# plugV6.net
KiCad netlist of a schematic drawn in EAGLE
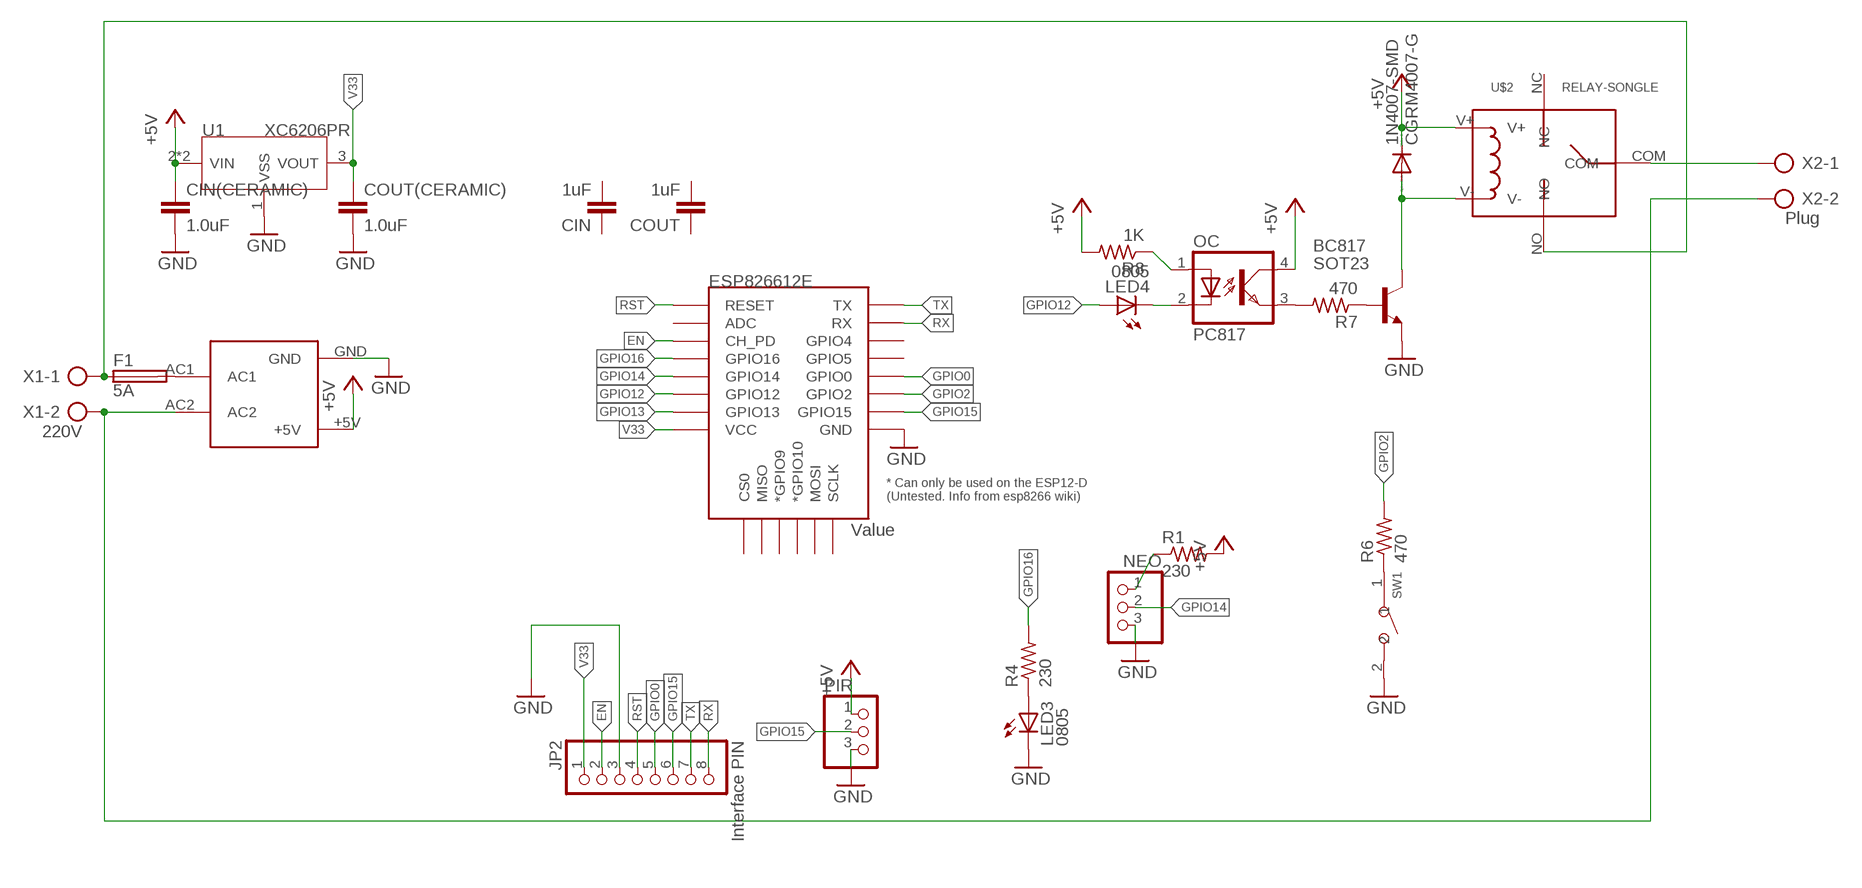
[diagram p0: schematic, sheet 1]

(export (version "E")
  (design (tool "Eeschema 10.0.6"))
  (components
    (comp (ref "1N4007-SMD")
      (value "CGRM4007-G")
      (footprint "eagle-import:SOD-123_MINI-SMA")
      (libsource (lib "eagle-import") (part "CGRM400-G7"))
    )
    (comp (ref "BC817")
      (value "SOT23")
      (footprint "eagle-import:SOT23-BEC")
      (libsource (lib "eagle-import") (part "-NPN-SOT23-BECBC817"))
    )
    (comp (ref "CIN")
      (value "1uF")
      (footprint "eagle-import:C0805")
      (libsource (lib "eagle-import") (part "C-EUC0805"))
    )
    (comp (ref "CIN(CERAMIC)")
      (value "1.0uF")
      (footprint "eagle-import:0402-CAP")
      (libsource (lib "eagle-import") (part "1.0UF-16V-10%(0402)"))
    )
    (comp (ref "COUT")
      (value "1uF")
      (footprint "eagle-import:C0805")
      (libsource (lib "eagle-import") (part "C-EUC0805"))
    )
    (comp (ref "COUT(CERAMIC)")
      (value "1.0uF")
      (footprint "eagle-import:0402-CAP")
      (libsource (lib "eagle-import") (part "1.0UF-16V-10%(0402)"))
    )
    (comp (ref "ESP826612E")
      (value "Value")
      (footprint "eagle-import:ESP12E-SMD")
      (libsource (lib "eagle-import") (part "ESP12ESMD"))
    )
    (comp (ref "F1")
      (value "5A")
      (footprint "eagle-import:SH22,5A")
      (fields (field (name "MPN") "0031.7701.11"))
      (libsource (lib "eagle-import") (part "SH22,5A"))
    )
    (comp (ref "JP2")
      (value "Interface PIN")
      (footprint "eagle-import:1X08")
      (libsource (lib "eagle-import") (part "PINHD-1X8"))
    )
    (comp (ref "LED3")
      (value "0805")
      (footprint "eagle-import:CHIP-LED0603")
      (libsource (lib "eagle-import") (part "LEDCHIP-LED0603"))
    )
    (comp (ref "LED4")
      (value "0805")
      (footprint "eagle-import:CHIP-LED0603")
      (libsource (lib "eagle-import") (part "LEDCHIP-LED0603"))
    )
    (comp (ref "NEO")
      (value "PINHD-1X3")
      (footprint "eagle-import:1X03")
      (libsource (lib "eagle-import") (part "PINHD-1X3"))
    )
    (comp (ref "OC")
      (value "PC817")
      (footprint "eagle-import:DIL04")
      (fields (field (name "MPN") "PC817X4J000F"))
      (libsource (lib "eagle-import") (part "PC817"))
    )
    (comp (ref "PIR")
      (value "PINHD-1X3")
      (footprint "eagle-import:1X03")
      (libsource (lib "eagle-import") (part "PINHD-1X3"))
    )
    (comp (ref "R1")
      (value "230")
      (footprint "eagle-import:R1206")
      (libsource (lib "eagle-import") (part "R-US_R1206"))
    )
    (comp (ref "R4")
      (value "230")
      (footprint "eagle-import:R1206")
      (libsource (lib "eagle-import") (part "R-US_R1206"))
    )
    (comp (ref "R6")
      (value "470")
      (footprint "eagle-import:R1206")
      (libsource (lib "eagle-import") (part "R-US_R1206"))
    )
    (comp (ref "R7")
      (value "470")
      (footprint "eagle-import:R1206")
      (libsource (lib "eagle-import") (part "R-US_R1206"))
    )
    (comp (ref "R8")
      (value "1K")
      (footprint "eagle-import:R1206")
      (libsource (lib "eagle-import") (part "R-US_R1206"))
    )
    (comp (ref "SW1")
      (value "DIP-BUTTON(2P-6.0X3.0X4.3MM)-TS-1101F")
      (footprint "eagle-import:SW2-5.0-6.0X3.0X4.3MM")
      (libsource (lib "eagle-import") (part "DIP-BUTTON(2P-6.0X3.0X4.3MM)-TS-1101F"))
    )
    (comp (ref "U$1")
      (value "HLK-PM01")
      (footprint "eagle-import:HLK-PM01")
      (libsource (lib "eagle-import") (part "HLK-PM01"))
    )
    (comp (ref "U$2")
      (value "RELAY-SONGLE")
      (footprint "eagle-import:RELAY-SONGLE")
      (libsource (lib "eagle-import") (part "RELAY-SONGLE"))
    )
    (comp (ref "U1")
      (value "XC6206PR")
      (footprint "eagle-import:SOT89")
      (libsource (lib "eagle-import") (part "XC6206PR"))
    )
    (comp (ref "X1")
      (value "220V")
      (footprint "eagle-import:AK300_2")
      (libsource (lib "eagle-import") (part "AK300/2"))
    )
    (comp (ref "X2")
      (value "Plug")
      (footprint "eagle-import:AK300_2")
      (libsource (lib "eagle-import") (part "AK300/2"))
    )
  )
  (nets
    (net (code "1") (name "+5V") (class "Default")
      (node (ref "1N4007-SMD") (pin "C") (pinfunction "C_C") (pintype "passive"))
      (node (ref "CIN(CERAMIC)") (pin "1") (pinfunction "1_1") (pintype "passive"))
      (node (ref "OC") (pin "4") (pinfunction "COL_4") (pintype "passive"))
      (node (ref "PIR") (pin "1") (pinfunction "1_1") (pintype "passive"))
      (node (ref "R1") (pin "2") (pinfunction "2_2") (pintype "passive"))
      (node (ref "R8") (pin "2") (pinfunction "2_2") (pintype "passive"))
      (node (ref "U$1") (pin "+5V") (pinfunction "+5V_+5V") (pintype "bidirectional"))
      (node (ref "U$2") (pin "V+") (pinfunction "V+_V+") (pintype "bidirectional"))
      (node (ref "U1") (pin "2") (pinfunction "VIN_2") (pintype "input"))
      (node (ref "U1") (pin "4") (pinfunction "VIN_4") (pintype "input"))
    )
    (net (code "2") (name "EN") (class "Default")
      (node (ref "ESP826612E") (pin "CH_PD") (pinfunction "CH_PD_CH_PD") (pintype "bidirectional"))
      (node (ref "JP2") (pin "2") (pinfunction "2_2") (pintype "passive"))
    )
    (net (code "3") (name "GND") (class "Default")
      (node (ref "BC817") (pin "E") (pinfunction "E_E") (pintype "passive"))
      (node (ref "CIN(CERAMIC)") (pin "2") (pinfunction "2_2") (pintype "passive"))
      (node (ref "COUT(CERAMIC)") (pin "2") (pinfunction "2_2") (pintype "passive"))
      (node (ref "ESP826612E") (pin "GND") (pinfunction "GND_GND") (pintype "bidirectional"))
      (node (ref "JP2") (pin "3") (pinfunction "3_3") (pintype "passive"))
      (node (ref "LED3") (pin "C") (pinfunction "C_C") (pintype "passive"))
      (node (ref "NEO") (pin "3") (pinfunction "3_3") (pintype "passive"))
      (node (ref "PIR") (pin "3") (pinfunction "3_3") (pintype "passive"))
      (node (ref "SW1") (pin "2") (pinfunction "2_2") (pintype "bidirectional"))
      (node (ref "U$1") (pin "GND") (pinfunction "GND_GND") (pintype "bidirectional"))
      (node (ref "U1") (pin "1") (pinfunction "VSS_1") (pintype "power_in"))
    )
    (net (code "4") (name "GPIO0") (class "Default")
      (node (ref "ESP826612E") (pin "GPIO0") (pinfunction "GPIO0_GPIO0") (pintype "bidirectional"))
      (node (ref "JP2") (pin "5") (pinfunction "5_5") (pintype "passive"))
    )
    (net (code "5") (name "GPIO2") (class "Default")
      (node (ref "ESP826612E") (pin "GPIO2") (pinfunction "GPIO2_GPIO2") (pintype "bidirectional"))
      (node (ref "R6") (pin "2") (pinfunction "2_2") (pintype "passive"))
    )
    (net (code "6") (name "GPIO12") (class "Default")
      (node (ref "ESP826612E") (pin "GPIO12") (pinfunction "GPIO12_GPIO12") (pintype "bidirectional"))
      (node (ref "LED4") (pin "A") (pinfunction "A_A") (pintype "passive"))
    )
    (net (code "7") (name "GPIO13") (class "Default")
      (node (ref "ESP826612E") (pin "GPIO13") (pinfunction "GPIO13_GPIO13") (pintype "bidirectional"))
    )
    (net (code "8") (name "GPIO14") (class "Default")
      (node (ref "ESP826612E") (pin "GPIO14") (pinfunction "GPIO14_GPIO14") (pintype "bidirectional"))
      (node (ref "NEO") (pin "2") (pinfunction "2_2") (pintype "passive"))
    )
    (net (code "9") (name "GPIO15") (class "Default")
      (node (ref "ESP826612E") (pin "GPIO15") (pinfunction "GPIO15_GPIO15") (pintype "bidirectional"))
      (node (ref "JP2") (pin "6") (pinfunction "6_6") (pintype "passive"))
      (node (ref "PIR") (pin "2") (pinfunction "2_2") (pintype "passive"))
    )
    (net (code "10") (name "GPIO16") (class "Default")
      (node (ref "ESP826612E") (pin "GPIO16") (pinfunction "GPIO16_GPIO16") (pintype "bidirectional"))
      (node (ref "R4") (pin "2") (pinfunction "2_2") (pintype "passive"))
    )
    (net (code "11") (name "Net-(1N4007-SMD-PadA)") (class "Default")
      (node (ref "1N4007-SMD") (pin "A") (pinfunction "A_A") (pintype "passive"))
      (node (ref "BC817") (pin "C") (pinfunction "C_C") (pintype "passive"))
      (node (ref "U$2") (pin "V-") (pinfunction "V-_V-") (pintype "bidirectional"))
    )
    (net (code "12") (name "Net-(BC817-PadB)") (class "Default")
      (node (ref "BC817") (pin "B") (pinfunction "B_B") (pintype "passive"))
      (node (ref "R7") (pin "1") (pinfunction "1_1") (pintype "passive"))
    )
    (net (code "13") (name "Net-(F1-Pad2)") (class "Default")
      (node (ref "F1") (pin "2") (pinfunction "2_2") (pintype "passive"))
      (node (ref "U$1") (pin "AC1") (pinfunction "AC1_AC1") (pintype "bidirectional"))
    )
    (net (code "14") (name "Net-(LED3-PadA)") (class "Default")
      (node (ref "LED3") (pin "A") (pinfunction "A_A") (pintype "passive"))
      (node (ref "R4") (pin "1") (pinfunction "1_1") (pintype "passive"))
    )
    (net (code "15") (name "Net-(NEO-Pad1)") (class "Default")
      (node (ref "NEO") (pin "1") (pinfunction "1_1") (pintype "passive"))
      (node (ref "R1") (pin "1") (pinfunction "1_1") (pintype "passive"))
    )
    (net (code "16") (name "Net-(OC-A)") (class "Default")
      (node (ref "OC") (pin "1") (pinfunction "A_1") (pintype "passive"))
      (node (ref "R8") (pin "1") (pinfunction "1_1") (pintype "passive"))
    )
    (net (code "17") (name "Net-(OC-C)") (class "Default")
      (node (ref "LED4") (pin "C") (pinfunction "C_C") (pintype "passive"))
      (node (ref "OC") (pin "2") (pinfunction "C_2") (pintype "passive"))
    )
    (net (code "18") (name "Net-(OC-EMIT)") (class "Default")
      (node (ref "OC") (pin "3") (pinfunction "EMIT_3") (pintype "passive"))
      (node (ref "R7") (pin "2") (pinfunction "2_2") (pintype "passive"))
    )
    (net (code "19") (name "Net-(R6-Pad1)") (class "Default")
      (node (ref "R6") (pin "1") (pinfunction "1_1") (pintype "passive"))
      (node (ref "SW1") (pin "1") (pinfunction "1_1") (pintype "bidirectional"))
    )
    (net (code "20") (name "Net-(X1A-KL)") (class "Default")
      (node (ref "F1") (pin "1") (pinfunction "1_1") (pintype "passive"))
      (node (ref "U$2") (pin "NO") (pinfunction "NO_NO") (pintype "bidirectional"))
      (node (ref "X1") (pin "1") (pinfunction "KL_1") (pintype "passive"))
    )
    (net (code "21") (name "Net-(X1B-KL)") (class "Default")
      (node (ref "U$1") (pin "AC2") (pinfunction "AC2_AC2") (pintype "bidirectional"))
      (node (ref "X1") (pin "2") (pinfunction "KL_2") (pintype "passive"))
      (node (ref "X2") (pin "2") (pinfunction "KL_2") (pintype "passive"))
    )
    (net (code "22") (name "Net-(X2A-KL)") (class "Default")
      (node (ref "U$2") (pin "COM") (pinfunction "COM_COM") (pintype "bidirectional"))
      (node (ref "X2") (pin "1") (pinfunction "KL_1") (pintype "passive"))
    )
    (net (code "23") (name "RST") (class "Default")
      (node (ref "ESP826612E") (pin "RESET") (pinfunction "RESET_RESET") (pintype "bidirectional"))
      (node (ref "JP2") (pin "4") (pinfunction "4_4") (pintype "passive"))
    )
    (net (code "24") (name "RX") (class "Default")
      (node (ref "ESP826612E") (pin "RXD0") (pinfunction "RX_RXD0") (pintype "bidirectional"))
      (node (ref "JP2") (pin "8") (pinfunction "8_8") (pintype "passive"))
    )
    (net (code "25") (name "TX") (class "Default")
      (node (ref "ESP826612E") (pin "TXD0") (pinfunction "TX_TXD0") (pintype "bidirectional"))
      (node (ref "JP2") (pin "7") (pinfunction "7_7") (pintype "passive"))
    )
    (net (code "26") (name "V33") (class "Default")
      (node (ref "COUT(CERAMIC)") (pin "1") (pinfunction "1_1") (pintype "passive"))
      (node (ref "ESP826612E") (pin "VCC") (pinfunction "VCC_VCC") (pintype "bidirectional"))
      (node (ref "JP2") (pin "1") (pinfunction "1_1") (pintype "passive"))
      (node (ref "U1") (pin "3") (pinfunction "VOUT_3") (pintype "output"))
    )
    (net (code "27") (name "unconnected-(CIN-Pad1)") (class "Default")
      (node (ref "CIN") (pin "1") (pinfunction "1_1") (pintype "passive"))
    )
    (net (code "28") (name "unconnected-(CIN-Pad2)") (class "Default")
      (node (ref "CIN") (pin "2") (pinfunction "2_2") (pintype "passive"))
    )
    (net (code "29") (name "unconnected-(COUT-Pad1)") (class "Default")
      (node (ref "COUT") (pin "1") (pinfunction "1_1") (pintype "passive"))
    )
    (net (code "30") (name "unconnected-(COUT-Pad2)") (class "Default")
      (node (ref "COUT") (pin "2") (pinfunction "2_2") (pintype "passive"))
    )
    (net (code "31") (name "unconnected-(ESP826612E-*GPIO9-PadGPIO9)") (class "Default")
      (node (ref "ESP826612E") (pin "GPIO9") (pinfunction "*GPIO9_GPIO9") (pintype "bidirectional"))
    )
    (net (code "32") (name "unconnected-(ESP826612E-*GPIO10-PadGPIO10)") (class "Default")
      (node (ref "ESP826612E") (pin "GPIO10") (pinfunction "*GPIO10_GPIO10") (pintype "bidirectional"))
    )
    (net (code "33") (name "unconnected-(ESP826612E-PadADC)") (class "Default")
      (node (ref "ESP826612E") (pin "ADC") (pinfunction "ADC_ADC") (pintype "bidirectional"))
    )
    (net (code "34") (name "unconnected-(ESP826612E-PadCS0)") (class "Default")
      (node (ref "ESP826612E") (pin "CS0") (pinfunction "CS0_CS0") (pintype "bidirectional"))
    )
    (net (code "35") (name "unconnected-(ESP826612E-PadGPIO4)") (class "Default")
      (node (ref "ESP826612E") (pin "GPIO4") (pinfunction "GPIO4_GPIO4") (pintype "bidirectional"))
    )
    (net (code "36") (name "unconnected-(ESP826612E-PadGPIO5)") (class "Default")
      (node (ref "ESP826612E") (pin "GPIO5") (pinfunction "GPIO5_GPIO5") (pintype "bidirectional"))
    )
    (net (code "37") (name "unconnected-(ESP826612E-PadMISO)") (class "Default")
      (node (ref "ESP826612E") (pin "MISO") (pinfunction "MISO_MISO") (pintype "bidirectional"))
    )
    (net (code "38") (name "unconnected-(ESP826612E-PadMOSI)") (class "Default")
      (node (ref "ESP826612E") (pin "MOSI") (pinfunction "MOSI_MOSI") (pintype "bidirectional"))
    )
    (net (code "39") (name "unconnected-(ESP826612E-PadSCLK)") (class "Default")
      (node (ref "ESP826612E") (pin "SCLK") (pinfunction "SCLK_SCLK") (pintype "bidirectional"))
    )
    (net (code "40") (name "unconnected-(U$2-PadNC)") (class "Default")
      (node (ref "U$2") (pin "NC") (pinfunction "NC_NC") (pintype "bidirectional"))
    )
  )
)
